# Display.net
KiCad netlist of a schematic drawn in Altium Designer
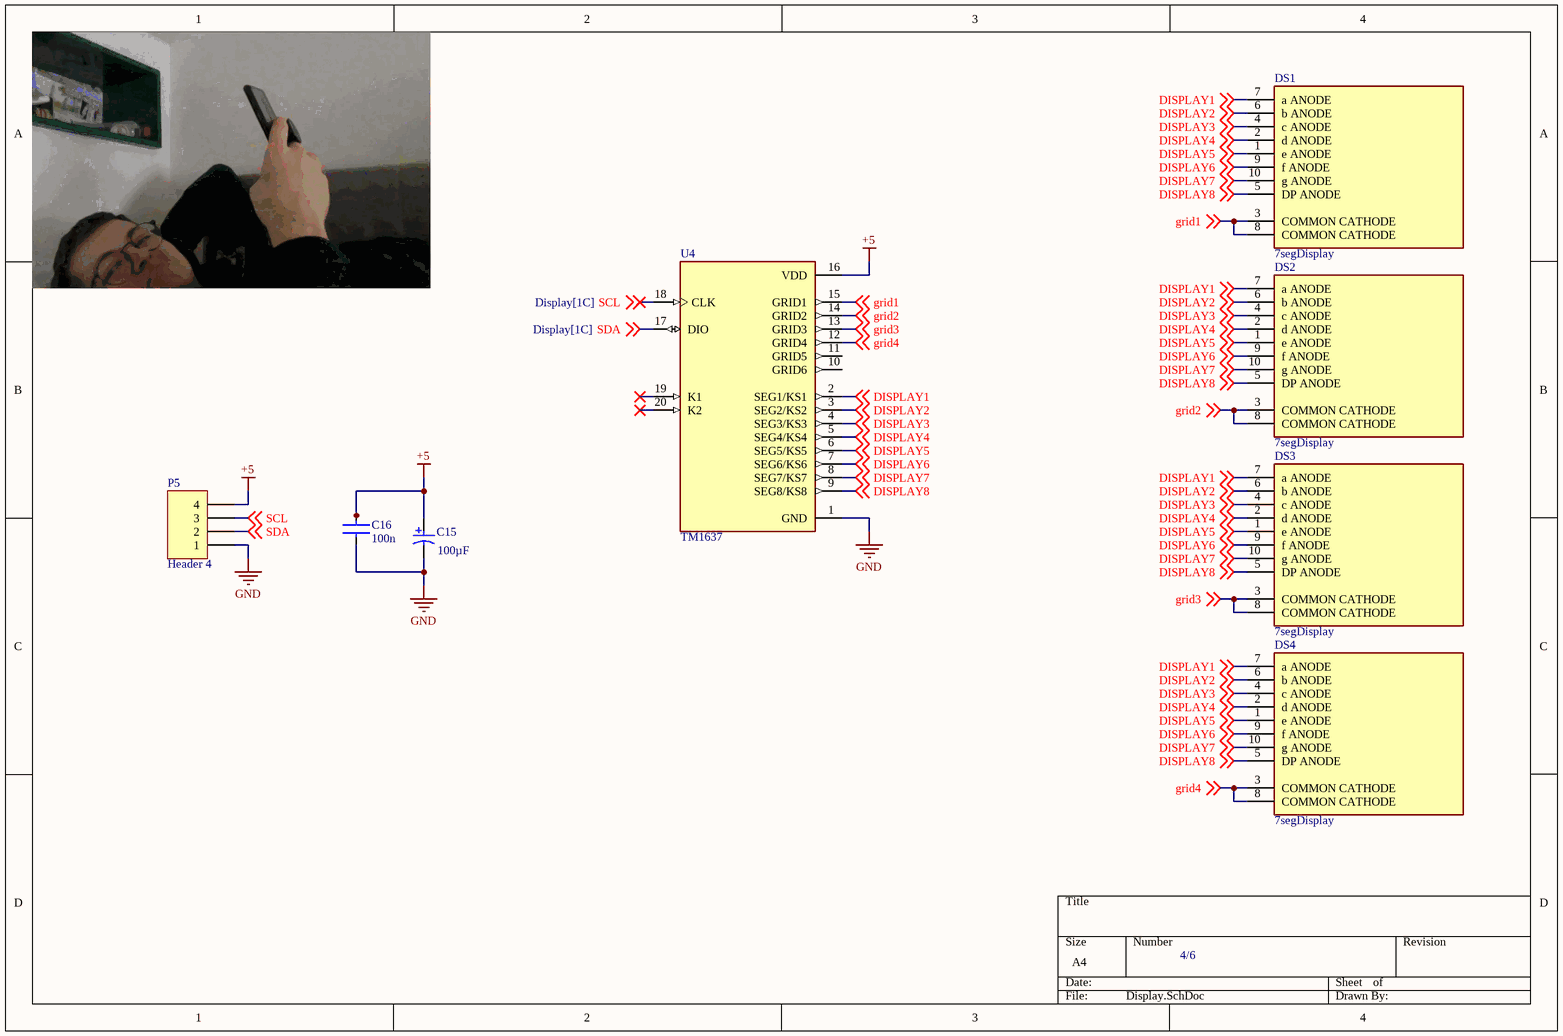
[diagram p0: Display.SchDoc]

(export (version "E")
  (design (tool "Eeschema 10.0.6"))
  (components
    (comp (ref "C15")
      (value "100µF")
      (footprint "CAP-SMD_BD8.0-L8.3-W8.3-FD")
      (fields (field (name "MANUFACTURER") "Panasonic"))
      (libsource (lib "Soldeerstation") (part "Electrolytic capacitor"))
    )
    (comp (ref "C16")
      (value "100n")
      (footprint "RESC2013X50X30LL20T20")
      (fields (field (name "VOLTAGE") "6.3V") (field (name "TOLERANCE") "20%"))
      (libsource (lib "Soldeerstation") (part "Capacitor"))
    )
    (comp (ref "DS1")
      (value "7segDisplay")
      (footprint "FP-ACSC02-41SURKWA-F01-MFG")
      (description "DISPLAY 7-SEG 0.2\" SGL RED 10SMD")
      (libsource (lib "Soldeerstation") (part "7segDisplay"))
    )
    (comp (ref "DS2")
      (value "7segDisplay")
      (footprint "FP-ACSC02-41SURKWA-F01-MFG")
      (description "DISPLAY 7-SEG 0.2\" SGL RED 10SMD")
      (libsource (lib "Soldeerstation") (part "7segDisplay"))
    )
    (comp (ref "DS3")
      (value "7segDisplay")
      (footprint "FP-ACSC02-41SURKWA-F01-MFG")
      (description "DISPLAY 7-SEG 0.2\" SGL RED 10SMD")
      (libsource (lib "Soldeerstation") (part "7segDisplay"))
    )
    (comp (ref "DS4")
      (value "7segDisplay")
      (footprint "FP-ACSC02-41SURKWA-F01-MFG")
      (description "DISPLAY 7-SEG 0.2\" SGL RED 10SMD")
      (libsource (lib "Soldeerstation") (part "7segDisplay"))
    )
    (comp (ref "P5")
      (value "Header 4")
      (footprint "HDR1X4")
      (description "Header, 4-Pin")
      (fields (field (name "PUBLISHER") "Altium Limited"))
      (libsource (lib "Miscellaneous Connectors") (part "Header 4"))
    )
    (comp (ref "U4")
      (value "TM1637")
      (footprint "SOP_20_M")
      (description "LED Drive Control Special Circuit")
      (fields (field (name "MF") "Titan Micro Electronics"))
      (libsource (lib "Soldeerstation") (part "TM1637"))
    )
  )
  (nets
    (net (code "1") (name "+5") (class "Default")
      (node (ref "C15") (pin "1") (pinfunction "+_1") (pintype "passive"))
      (node (ref "C16") (pin "1") (pinfunction "1_1") (pintype "passive"))
      (node (ref "P5") (pin "4") (pinfunction "4_4") (pintype "passive"))
      (node (ref "U4") (pin "16") (pinfunction "VDD_16") (pintype "power_in"))
    )
    (net (code "2") (name "DISPLAY1") (class "Default")
      (node (ref "DS1") (pin "7") (pinfunction "a_ANODE_7") (pintype "passive"))
      (node (ref "DS2") (pin "7") (pinfunction "a_ANODE_7") (pintype "passive"))
      (node (ref "DS3") (pin "7") (pinfunction "a_ANODE_7") (pintype "passive"))
      (node (ref "DS4") (pin "7") (pinfunction "a_ANODE_7") (pintype "passive"))
      (node (ref "U4") (pin "2") (pinfunction "SEG1/KS1_2") (pintype "output"))
    )
    (net (code "3") (name "DISPLAY2") (class "Default")
      (node (ref "DS1") (pin "6") (pinfunction "b_ANODE_6") (pintype "passive"))
      (node (ref "DS2") (pin "6") (pinfunction "b_ANODE_6") (pintype "passive"))
      (node (ref "DS3") (pin "6") (pinfunction "b_ANODE_6") (pintype "passive"))
      (node (ref "DS4") (pin "6") (pinfunction "b_ANODE_6") (pintype "passive"))
      (node (ref "U4") (pin "3") (pinfunction "SEG2/KS2_3") (pintype "output"))
    )
    (net (code "4") (name "DISPLAY3") (class "Default")
      (node (ref "DS1") (pin "4") (pinfunction "c_ANODE_4") (pintype "passive"))
      (node (ref "DS2") (pin "4") (pinfunction "c_ANODE_4") (pintype "passive"))
      (node (ref "DS3") (pin "4") (pinfunction "c_ANODE_4") (pintype "passive"))
      (node (ref "DS4") (pin "4") (pinfunction "c_ANODE_4") (pintype "passive"))
      (node (ref "U4") (pin "4") (pinfunction "SEG3/KS3_4") (pintype "output"))
    )
    (net (code "5") (name "DISPLAY4") (class "Default")
      (node (ref "DS1") (pin "2") (pinfunction "d_ANODE_2") (pintype "passive"))
      (node (ref "DS2") (pin "2") (pinfunction "d_ANODE_2") (pintype "passive"))
      (node (ref "DS3") (pin "2") (pinfunction "d_ANODE_2") (pintype "passive"))
      (node (ref "DS4") (pin "2") (pinfunction "d_ANODE_2") (pintype "passive"))
      (node (ref "U4") (pin "5") (pinfunction "SEG4/KS4_5") (pintype "output"))
    )
    (net (code "6") (name "DISPLAY5") (class "Default")
      (node (ref "DS1") (pin "1") (pinfunction "e_ANODE_1") (pintype "passive"))
      (node (ref "DS2") (pin "1") (pinfunction "e_ANODE_1") (pintype "passive"))
      (node (ref "DS3") (pin "1") (pinfunction "e_ANODE_1") (pintype "passive"))
      (node (ref "DS4") (pin "1") (pinfunction "e_ANODE_1") (pintype "passive"))
      (node (ref "U4") (pin "6") (pinfunction "SEG5/KS5_6") (pintype "output"))
    )
    (net (code "7") (name "DISPLAY6") (class "Default")
      (node (ref "DS1") (pin "9") (pinfunction "f_ANODE_9") (pintype "passive"))
      (node (ref "DS2") (pin "9") (pinfunction "f_ANODE_9") (pintype "passive"))
      (node (ref "DS3") (pin "9") (pinfunction "f_ANODE_9") (pintype "passive"))
      (node (ref "DS4") (pin "9") (pinfunction "f_ANODE_9") (pintype "passive"))
      (node (ref "U4") (pin "7") (pinfunction "SEG6/KS6_7") (pintype "output"))
    )
    (net (code "8") (name "DISPLAY7") (class "Default")
      (node (ref "DS1") (pin "10") (pinfunction "g_ANODE_10") (pintype "passive"))
      (node (ref "DS2") (pin "10") (pinfunction "g_ANODE_10") (pintype "passive"))
      (node (ref "DS3") (pin "10") (pinfunction "g_ANODE_10") (pintype "passive"))
      (node (ref "DS4") (pin "10") (pinfunction "g_ANODE_10") (pintype "passive"))
      (node (ref "U4") (pin "8") (pinfunction "SEG7/KS7_8") (pintype "output"))
    )
    (net (code "9") (name "DISPLAY8") (class "Default")
      (node (ref "DS1") (pin "5") (pinfunction "DP_ANODE_5") (pintype "passive"))
      (node (ref "DS2") (pin "5") (pinfunction "DP_ANODE_5") (pintype "passive"))
      (node (ref "DS3") (pin "5") (pinfunction "DP_ANODE_5") (pintype "passive"))
      (node (ref "DS4") (pin "5") (pinfunction "DP_ANODE_5") (pintype "passive"))
      (node (ref "U4") (pin "9") (pinfunction "SEG8/KS8_9") (pintype "output"))
    )
    (net (code "10") (name "GND") (class "Default")
      (node (ref "C15") (pin "2") (pinfunction "-_2") (pintype "passive"))
      (node (ref "C16") (pin "2") (pinfunction "2_2") (pintype "passive"))
      (node (ref "P5") (pin "1") (pinfunction "1_1") (pintype "passive"))
      (node (ref "U4") (pin "1") (pinfunction "GND_1") (pintype "power_in"))
    )
    (net (code "11") (name "SCL") (class "Default")
      (node (ref "P5") (pin "3") (pinfunction "3_3") (pintype "passive"))
      (node (ref "U4") (pin "18") (pinfunction "CLK_18") (pintype "input"))
    )
    (net (code "12") (name "SDA") (class "Default")
      (node (ref "P5") (pin "2") (pinfunction "2_2") (pintype "passive"))
      (node (ref "U4") (pin "17") (pinfunction "DIO_17") (pintype "bidirectional"))
    )
    (net (code "13") (name "grid1") (class "Default")
      (node (ref "DS1") (pin "3") (pinfunction "COMMON_CATHODE_3") (pintype "passive"))
      (node (ref "DS1") (pin "8") (pinfunction "COMMON_CATHODE_8") (pintype "passive"))
      (node (ref "U4") (pin "15") (pinfunction "GRID1_15") (pintype "output"))
    )
    (net (code "14") (name "grid2") (class "Default")
      (node (ref "DS2") (pin "3") (pinfunction "COMMON_CATHODE_3") (pintype "passive"))
      (node (ref "DS2") (pin "8") (pinfunction "COMMON_CATHODE_8") (pintype "passive"))
      (node (ref "U4") (pin "14") (pinfunction "GRID2_14") (pintype "output"))
    )
    (net (code "15") (name "grid3") (class "Default")
      (node (ref "DS3") (pin "3") (pinfunction "COMMON_CATHODE_3") (pintype "passive"))
      (node (ref "DS3") (pin "8") (pinfunction "COMMON_CATHODE_8") (pintype "passive"))
      (node (ref "U4") (pin "13") (pinfunction "GRID3_13") (pintype "output"))
    )
    (net (code "16") (name "grid4") (class "Default")
      (node (ref "DS4") (pin "3") (pinfunction "COMMON_CATHODE_3") (pintype "passive"))
      (node (ref "DS4") (pin "8") (pinfunction "COMMON_CATHODE_8") (pintype "passive"))
      (node (ref "U4") (pin "12") (pinfunction "GRID4_12") (pintype "output"))
    )
    (net (code "17") (name "unconnected-(U4-GRID5-Pad11)") (class "Default")
      (node (ref "U4") (pin "11") (pinfunction "GRID5_11") (pintype "output"))
    )
    (net (code "18") (name "unconnected-(U4-GRID6-Pad10)") (class "Default")
      (node (ref "U4") (pin "10") (pinfunction "GRID6_10") (pintype "output"))
    )
    (net (code "19") (name "unconnected-(U4-K1-Pad19)") (class "Default")
      (node (ref "U4") (pin "19") (pinfunction "K1_19") (pintype "input+no_connect"))
    )
    (net (code "20") (name "unconnected-(U4-K2-Pad20)") (class "Default")
      (node (ref "U4") (pin "20") (pinfunction "K2_20") (pintype "input+no_connect"))
    )
  )
)
